# Power_Board.net
KiCad netlist of a schematic drawn in EAGLE
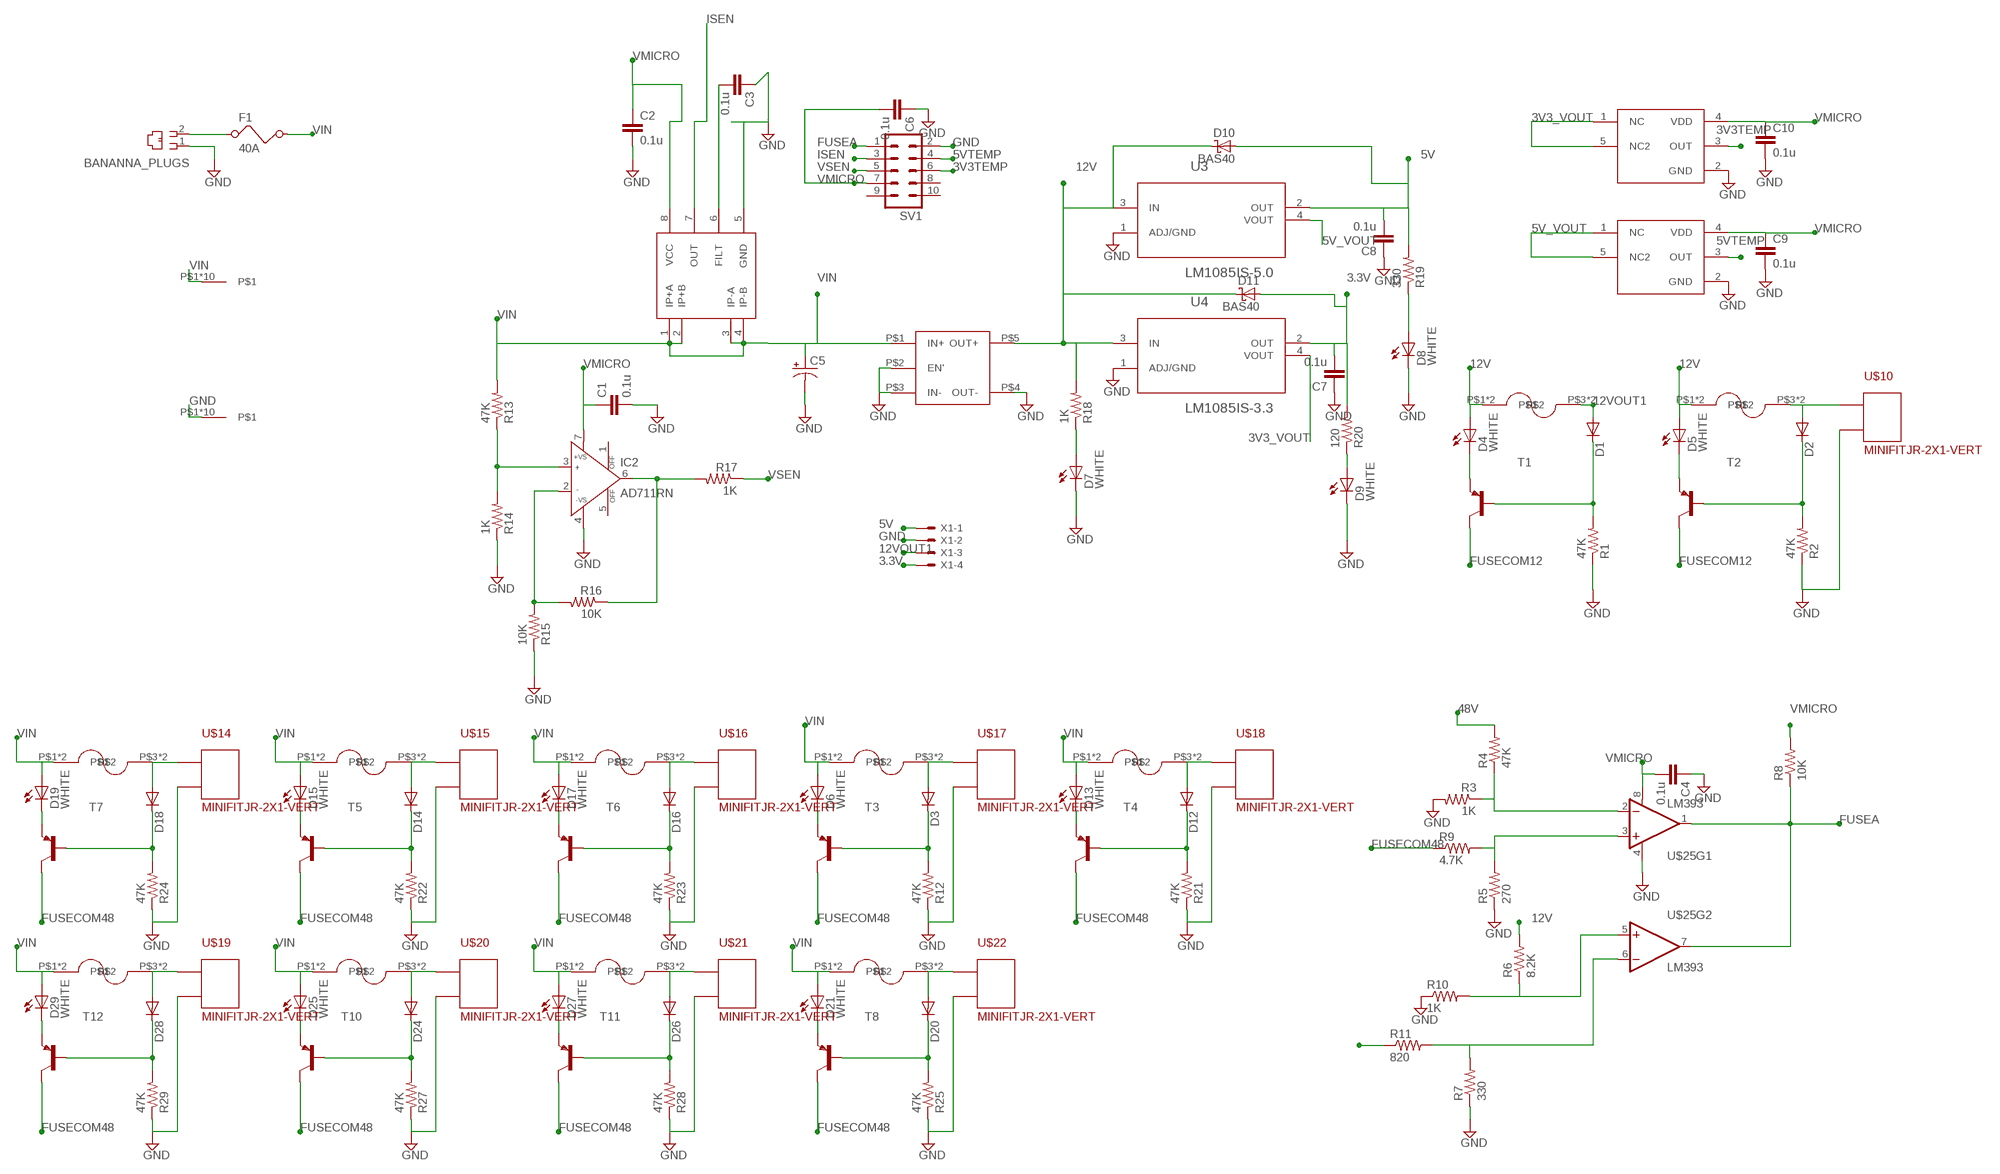
[diagram p0: schematic, sheet 1]

(export (version "E")
  (design (tool "Eeschema 10.0.6"))
  (components
    (comp (ref "BANANNA_PLUGS")
      (value "520470-4")
      (footprint "eagle-import:520470-4")
      (libsource (lib "eagle-import") (part "520470-4"))
    )
    (comp (ref "C1")
      (value "0.1u")
      (footprint "eagle-import:0805")
      (libsource (lib "eagle-import") (part "CAP0805"))
    )
    (comp (ref "C2")
      (value "0.1u")
      (footprint "eagle-import:0805")
      (libsource (lib "eagle-import") (part "CAP0805"))
    )
    (comp (ref "C3")
      (value "0.1u")
      (footprint "eagle-import:0805")
      (libsource (lib "eagle-import") (part "CAP0805"))
    )
    (comp (ref "C4")
      (value "0.1u")
      (footprint "eagle-import:0805")
      (libsource (lib "eagle-import") (part "CAP0805"))
    )
    (comp (ref "C5")
      (value "CPOL-USE10-30")
      (footprint "eagle-import:EB30D")
      (libsource (lib "eagle-import") (part "CPOL-USE10-30"))
    )
    (comp (ref "C6")
      (value "0.1u")
      (footprint "eagle-import:0805")
      (libsource (lib "eagle-import") (part "CAP0805"))
    )
    (comp (ref "C7")
      (value "0.1u")
      (footprint "eagle-import:0805")
      (libsource (lib "eagle-import") (part "CAP0805"))
    )
    (comp (ref "C8")
      (value "0.1u")
      (footprint "eagle-import:0805")
      (libsource (lib "eagle-import") (part "CAP0805"))
    )
    (comp (ref "C9")
      (value "0.1u")
      (footprint "eagle-import:0805")
      (libsource (lib "eagle-import") (part "CAP0805"))
    )
    (comp (ref "C10")
      (value "0.1u")
      (footprint "eagle-import:0805")
      (libsource (lib "eagle-import") (part "CAP0805"))
    )
    (comp (ref "D1")
      (value "DIODEHV")
      (footprint "eagle-import:DIODE-HV")
      (libsource (lib "eagle-import") (part "DIODEHV"))
    )
    (comp (ref "D2")
      (value "DIODEHV")
      (footprint "eagle-import:DIODE-HV")
      (libsource (lib "eagle-import") (part "DIODEHV"))
    )
    (comp (ref "D3")
      (value "DIODEHV")
      (footprint "eagle-import:DIODE-HV")
      (libsource (lib "eagle-import") (part "DIODEHV"))
    )
    (comp (ref "D4")
      (value "WHITE")
      (footprint "eagle-import:LED-1206")
      (libsource (lib "eagle-import") (part "LED-WHITE"))
    )
    (comp (ref "D5")
      (value "WHITE")
      (footprint "eagle-import:LED-1206")
      (libsource (lib "eagle-import") (part "LED-WHITE"))
    )
    (comp (ref "D6")
      (value "WHITE")
      (footprint "eagle-import:LED-1206")
      (libsource (lib "eagle-import") (part "LED-WHITE"))
    )
    (comp (ref "D7")
      (value "WHITE")
      (footprint "eagle-import:LED-1206")
      (libsource (lib "eagle-import") (part "LED-WHITE"))
    )
    (comp (ref "D8")
      (value "WHITE")
      (footprint "eagle-import:LED-1206")
      (libsource (lib "eagle-import") (part "LED-WHITE"))
    )
    (comp (ref "D9")
      (value "WHITE")
      (footprint "eagle-import:LED-1206")
      (libsource (lib "eagle-import") (part "LED-WHITE"))
    )
    (comp (ref "D10")
      (value "BAS40")
      (footprint "eagle-import:SOT23")
      (libsource (lib "eagle-import") (part "BAS40"))
    )
    (comp (ref "D11")
      (value "BAS40")
      (footprint "eagle-import:SOT23")
      (libsource (lib "eagle-import") (part "BAS40"))
    )
    (comp (ref "D12")
      (value "DIODEHV")
      (footprint "eagle-import:DIODE-HV")
      (libsource (lib "eagle-import") (part "DIODEHV"))
    )
    (comp (ref "D13")
      (value "WHITE")
      (footprint "eagle-import:LED-1206")
      (libsource (lib "eagle-import") (part "LED-WHITE"))
    )
    (comp (ref "D14")
      (value "DIODEHV")
      (footprint "eagle-import:DIODE-HV")
      (libsource (lib "eagle-import") (part "DIODEHV"))
    )
    (comp (ref "D15")
      (value "WHITE")
      (footprint "eagle-import:LED-1206")
      (libsource (lib "eagle-import") (part "LED-WHITE"))
    )
    (comp (ref "D16")
      (value "DIODEHV")
      (footprint "eagle-import:DIODE-HV")
      (libsource (lib "eagle-import") (part "DIODEHV"))
    )
    (comp (ref "D17")
      (value "WHITE")
      (footprint "eagle-import:LED-1206")
      (libsource (lib "eagle-import") (part "LED-WHITE"))
    )
    (comp (ref "D18")
      (value "DIODEHV")
      (footprint "eagle-import:DIODE-HV")
      (libsource (lib "eagle-import") (part "DIODEHV"))
    )
    (comp (ref "D19")
      (value "WHITE")
      (footprint "eagle-import:LED-1206")
      (libsource (lib "eagle-import") (part "LED-WHITE"))
    )
    (comp (ref "D20")
      (value "DIODEHV")
      (footprint "eagle-import:DIODE-HV")
      (libsource (lib "eagle-import") (part "DIODEHV"))
    )
    (comp (ref "D21")
      (value "WHITE")
      (footprint "eagle-import:LED-1206")
      (libsource (lib "eagle-import") (part "LED-WHITE"))
    )
    (comp (ref "D24")
      (value "DIODEHV")
      (footprint "eagle-import:DIODE-HV")
      (libsource (lib "eagle-import") (part "DIODEHV"))
    )
    (comp (ref "D25")
      (value "WHITE")
      (footprint "eagle-import:LED-1206")
      (libsource (lib "eagle-import") (part "LED-WHITE"))
    )
    (comp (ref "D26")
      (value "DIODEHV")
      (footprint "eagle-import:DIODE-HV")
      (libsource (lib "eagle-import") (part "DIODEHV"))
    )
    (comp (ref "D27")
      (value "WHITE")
      (footprint "eagle-import:LED-1206")
      (libsource (lib "eagle-import") (part "LED-WHITE"))
    )
    (comp (ref "D28")
      (value "DIODEHV")
      (footprint "eagle-import:DIODE-HV")
      (libsource (lib "eagle-import") (part "DIODEHV"))
    )
    (comp (ref "D29")
      (value "WHITE")
      (footprint "eagle-import:LED-1206")
      (libsource (lib "eagle-import") (part "LED-WHITE"))
    )
    (comp (ref "F1")
      (value "40A")
      (footprint "eagle-import:FUSE")
      (libsource (lib "eagle-import") (part "FUSE"))
    )
    (comp (ref "IC2")
      (value "AD711RN")
      (footprint "eagle-import:SO8")
      (fields (field (name "MF") "ALTERA CORPORATION") (field (name "MPN") "AD711KRZ"))
      (libsource (lib "eagle-import") (part "AD711RN"))
    )
    (comp (ref "R1")
      (value "47K")
      (footprint "eagle-import:0805")
      (libsource (lib "eagle-import") (part "RESISTOR0805-RES"))
    )
    (comp (ref "R2")
      (value "47K")
      (footprint "eagle-import:0805")
      (libsource (lib "eagle-import") (part "RESISTOR0805-RES"))
    )
    (comp (ref "R3")
      (value "1K")
      (footprint "eagle-import:0805")
      (libsource (lib "eagle-import") (part "RESISTOR0805-RES"))
    )
    (comp (ref "R4")
      (value "47K")
      (footprint "eagle-import:0805")
      (libsource (lib "eagle-import") (part "RESISTOR0805-RES"))
    )
    (comp (ref "R5")
      (value "270")
      (footprint "eagle-import:0805")
      (libsource (lib "eagle-import") (part "RESISTOR0805-RES"))
    )
    (comp (ref "R6")
      (value "8.2K")
      (footprint "eagle-import:0805")
      (libsource (lib "eagle-import") (part "RESISTOR0805-RES"))
    )
    (comp (ref "R7")
      (value "330")
      (footprint "eagle-import:0805")
      (libsource (lib "eagle-import") (part "RESISTOR0805-RES"))
    )
    (comp (ref "R8")
      (value "10K")
      (footprint "eagle-import:0805")
      (libsource (lib "eagle-import") (part "RESISTOR0805-RES"))
    )
    (comp (ref "R9")
      (value "4.7K")
      (footprint "eagle-import:0805")
      (libsource (lib "eagle-import") (part "RESISTOR0805-RES"))
    )
    (comp (ref "R10")
      (value "1K")
      (footprint "eagle-import:0805")
      (libsource (lib "eagle-import") (part "RESISTOR0805-RES"))
    )
    (comp (ref "R11")
      (value "820")
      (footprint "eagle-import:0805")
      (libsource (lib "eagle-import") (part "RESISTOR0805-RES"))
    )
    (comp (ref "R12")
      (value "47K")
      (footprint "eagle-import:0805")
      (libsource (lib "eagle-import") (part "RESISTOR0805-RES"))
    )
    (comp (ref "R13")
      (value "47K")
      (footprint "eagle-import:0805")
      (libsource (lib "eagle-import") (part "RESISTOR0805-RES"))
    )
    (comp (ref "R14")
      (value "1K")
      (footprint "eagle-import:0805")
      (libsource (lib "eagle-import") (part "RESISTOR0805-RES"))
    )
    (comp (ref "R15")
      (value "10K")
      (footprint "eagle-import:0805")
      (libsource (lib "eagle-import") (part "RESISTOR0805-RES"))
    )
    (comp (ref "R16")
      (value "10K")
      (footprint "eagle-import:0805")
      (libsource (lib "eagle-import") (part "RESISTOR0805-RES"))
    )
    (comp (ref "R17")
      (value "1K")
      (footprint "eagle-import:0805")
      (libsource (lib "eagle-import") (part "RESISTOR0805-RES"))
    )
    (comp (ref "R18")
      (value "1K")
      (footprint "eagle-import:0805")
      (libsource (lib "eagle-import") (part "RESISTOR0805-RES"))
    )
    (comp (ref "R19")
      (value "330")
      (footprint "eagle-import:0805")
      (libsource (lib "eagle-import") (part "RESISTOR0805-RES"))
    )
    (comp (ref "R20")
      (value "120")
      (footprint "eagle-import:0805")
      (libsource (lib "eagle-import") (part "RESISTOR0805-RES"))
    )
    (comp (ref "R21")
      (value "47K")
      (footprint "eagle-import:0805")
      (libsource (lib "eagle-import") (part "RESISTOR0805-RES"))
    )
    (comp (ref "R22")
      (value "47K")
      (footprint "eagle-import:0805")
      (libsource (lib "eagle-import") (part "RESISTOR0805-RES"))
    )
    (comp (ref "R23")
      (value "47K")
      (footprint "eagle-import:0805")
      (libsource (lib "eagle-import") (part "RESISTOR0805-RES"))
    )
    (comp (ref "R24")
      (value "47K")
      (footprint "eagle-import:0805")
      (libsource (lib "eagle-import") (part "RESISTOR0805-RES"))
    )
    (comp (ref "R25")
      (value "47K")
      (footprint "eagle-import:0805")
      (libsource (lib "eagle-import") (part "RESISTOR0805-RES"))
    )
    (comp (ref "R27")
      (value "47K")
      (footprint "eagle-import:0805")
      (libsource (lib "eagle-import") (part "RESISTOR0805-RES"))
    )
    (comp (ref "R28")
      (value "47K")
      (footprint "eagle-import:0805")
      (libsource (lib "eagle-import") (part "RESISTOR0805-RES"))
    )
    (comp (ref "R29")
      (value "47K")
      (footprint "eagle-import:0805")
      (libsource (lib "eagle-import") (part "RESISTOR0805-RES"))
    )
    (comp (ref "SV1")
      (value "MA05-2")
      (footprint "eagle-import:MA05-2")
      (libsource (lib "eagle-import") (part "MA05-2"))
    )
    (comp (ref "T1")
      (value "BC856BLT1-PNP-SOT23-BEC")
      (footprint "eagle-import:SOT23-BEC")
      (libsource (lib "eagle-import") (part "-PNP-SOT23-BECBC856BLT1"))
    )
    (comp (ref "T2")
      (value "BC856BLT1-PNP-SOT23-BEC")
      (footprint "eagle-import:SOT23-BEC")
      (libsource (lib "eagle-import") (part "-PNP-SOT23-BECBC856BLT1"))
    )
    (comp (ref "T3")
      (value "BC856BLT1-PNP-SOT23-BEC")
      (footprint "eagle-import:SOT23-BEC")
      (libsource (lib "eagle-import") (part "-PNP-SOT23-BECBC856BLT1"))
    )
    (comp (ref "T4")
      (value "BC856BLT1-PNP-SOT23-BEC")
      (footprint "eagle-import:SOT23-BEC")
      (libsource (lib "eagle-import") (part "-PNP-SOT23-BECBC856BLT1"))
    )
    (comp (ref "T5")
      (value "BC856BLT1-PNP-SOT23-BEC")
      (footprint "eagle-import:SOT23-BEC")
      (libsource (lib "eagle-import") (part "-PNP-SOT23-BECBC856BLT1"))
    )
    (comp (ref "T6")
      (value "BC856BLT1-PNP-SOT23-BEC")
      (footprint "eagle-import:SOT23-BEC")
      (libsource (lib "eagle-import") (part "-PNP-SOT23-BECBC856BLT1"))
    )
    (comp (ref "T7")
      (value "BC856BLT1-PNP-SOT23-BEC")
      (footprint "eagle-import:SOT23-BEC")
      (libsource (lib "eagle-import") (part "-PNP-SOT23-BECBC856BLT1"))
    )
    (comp (ref "T8")
      (value "BC856BLT1-PNP-SOT23-BEC")
      (footprint "eagle-import:SOT23-BEC")
      (libsource (lib "eagle-import") (part "-PNP-SOT23-BECBC856BLT1"))
    )
    (comp (ref "T10")
      (value "BC856BLT1-PNP-SOT23-BEC")
      (footprint "eagle-import:SOT23-BEC")
      (libsource (lib "eagle-import") (part "-PNP-SOT23-BECBC856BLT1"))
    )
    (comp (ref "T11")
      (value "BC856BLT1-PNP-SOT23-BEC")
      (footprint "eagle-import:SOT23-BEC")
      (libsource (lib "eagle-import") (part "-PNP-SOT23-BECBC856BLT1"))
    )
    (comp (ref "T12")
      (value "BC856BLT1-PNP-SOT23-BEC")
      (footprint "eagle-import:SOT23-BEC")
      (libsource (lib "eagle-import") (part "-PNP-SOT23-BECBC856BLT1"))
    )
    (comp (ref "U$1")
      (value "SQE48T20120")
      (footprint "eagle-import:BRICK")
      (libsource (lib "eagle-import") (part "SQE48T20120"))
    )
    (comp (ref "U$2")
      (value "FUSEHOLDER3557-2")
      (footprint "eagle-import:FUSEHOLDER3557-2")
      (libsource (lib "eagle-import") (part "FUSEHOLDER3557-2"))
    )
    (comp (ref "U$3")
      (value "FUSEHOLDER3557-2")
      (footprint "eagle-import:FUSEHOLDER3557-2")
      (libsource (lib "eagle-import") (part "FUSEHOLDER3557-2"))
    )
    (comp (ref "U$4")
      (value "FUSEHOLDER3557-2")
      (footprint "eagle-import:FUSEHOLDER3557-2")
      (libsource (lib "eagle-import") (part "FUSEHOLDER3557-2"))
    )
    (comp (ref "U$5")
      (value "FUSEHOLDER3557-2")
      (footprint "eagle-import:FUSEHOLDER3557-2")
      (libsource (lib "eagle-import") (part "FUSEHOLDER3557-2"))
    )
    (comp (ref "U$6")
      (value "FUSEHOLDER3557-2")
      (footprint "eagle-import:FUSEHOLDER3557-2")
      (libsource (lib "eagle-import") (part "FUSEHOLDER3557-2"))
    )
    (comp (ref "U$7")
      (value "FUSEHOLDER3557-2")
      (footprint "eagle-import:FUSEHOLDER3557-2")
      (libsource (lib "eagle-import") (part "FUSEHOLDER3557-2"))
    )
    (comp (ref "U$8")
      (value "FUSEHOLDER3557-2")
      (footprint "eagle-import:FUSEHOLDER3557-2")
      (libsource (lib "eagle-import") (part "FUSEHOLDER3557-2"))
    )
    (comp (ref "U$9")
      (value "FUSEHOLDER3557-2")
      (footprint "eagle-import:FUSEHOLDER3557-2")
      (libsource (lib "eagle-import") (part "FUSEHOLDER3557-2"))
    )
    (comp (ref "U$10")
      (value "MINIFITJR-2X1-VERT")
      (footprint "eagle-import:5566-02B")
      (libsource (lib "eagle-import") (part "MINIFITJR-2X1-VERT"))
    )
    (comp (ref "U$11")
      (value "FUSEHOLDER3557-2")
      (footprint "eagle-import:FUSEHOLDER3557-2")
      (libsource (lib "eagle-import") (part "FUSEHOLDER3557-2"))
    )
    (comp (ref "U$12")
      (value "FUSEHOLDER3557-2")
      (footprint "eagle-import:FUSEHOLDER3557-2")
      (libsource (lib "eagle-import") (part "FUSEHOLDER3557-2"))
    )
    (comp (ref "U$13")
      (value "FUSEHOLDER3557-2")
      (footprint "eagle-import:FUSEHOLDER3557-2")
      (libsource (lib "eagle-import") (part "FUSEHOLDER3557-2"))
    )
    (comp (ref "U$14")
      (value "MINIFITJR-2X1-VERT")
      (footprint "eagle-import:5566-02B")
      (libsource (lib "eagle-import") (part "MINIFITJR-2X1-VERT"))
    )
    (comp (ref "U$15")
      (value "MINIFITJR-2X1-VERT")
      (footprint "eagle-import:5566-02B")
      (libsource (lib "eagle-import") (part "MINIFITJR-2X1-VERT"))
    )
    (comp (ref "U$16")
      (value "MINIFITJR-2X1-VERT")
      (footprint "eagle-import:5566-02B")
      (libsource (lib "eagle-import") (part "MINIFITJR-2X1-VERT"))
    )
    (comp (ref "U$17")
      (value "MINIFITJR-2X1-VERT")
      (footprint "eagle-import:5566-02B")
      (libsource (lib "eagle-import") (part "MINIFITJR-2X1-VERT"))
    )
    (comp (ref "U$18")
      (value "MINIFITJR-2X1-VERT")
      (footprint "eagle-import:5566-02B")
      (libsource (lib "eagle-import") (part "MINIFITJR-2X1-VERT"))
    )
    (comp (ref "U$19")
      (value "MINIFITJR-2X1-VERT")
      (footprint "eagle-import:5566-02B")
      (libsource (lib "eagle-import") (part "MINIFITJR-2X1-VERT"))
    )
    (comp (ref "U$20")
      (value "MINIFITJR-2X1-VERT")
      (footprint "eagle-import:5566-02B")
      (libsource (lib "eagle-import") (part "MINIFITJR-2X1-VERT"))
    )
    (comp (ref "U$21")
      (value "MINIFITJR-2X1-VERT")
      (footprint "eagle-import:5566-02B")
      (libsource (lib "eagle-import") (part "MINIFITJR-2X1-VERT"))
    )
    (comp (ref "U$22")
      (value "MINIFITJR-2X1-VERT")
      (footprint "eagle-import:5566-02B")
      (libsource (lib "eagle-import") (part "MINIFITJR-2X1-VERT"))
    )
    (comp (ref "U$25")
      (value "LM393")
      (footprint "eagle-import:SO08")
      (libsource (lib "eagle-import") (part "LM393"))
    )
    (comp (ref "U$26")
      (value "MCP9700T")
      (footprint "eagle-import:SOT353")
      (libsource (lib "eagle-import") (part "MCP9700T"))
    )
    (comp (ref "U$27")
      (value "MCP9700T")
      (footprint "eagle-import:SOT353")
      (libsource (lib "eagle-import") (part "MCP9700T"))
    )
    (comp (ref "U$30")
      (value "SCREW_TERM")
      (footprint "eagle-import:TERMINAL")
      (libsource (lib "eagle-import") (part "SCREW_TERM"))
    )
    (comp (ref "U$31")
      (value "SCREW_TERM")
      (footprint "eagle-import:TERMINAL")
      (libsource (lib "eagle-import") (part "SCREW_TERM"))
    )
    (comp (ref "U$32")
      (value "ACS713")
      (footprint "eagle-import:SOP08")
      (libsource (lib "eagle-import") (part "ACS713"))
    )
    (comp (ref "U3")
      (value "LM1085IS-5.0")
      (footprint "eagle-import:TO254P1435X457-3N")
      (libsource (lib "eagle-import") (part "LM1085IS-5.0"))
    )
    (comp (ref "U4")
      (value "LM1085IS-3.3")
      (footprint "eagle-import:TO254P1435X457-3N")
      (libsource (lib "eagle-import") (part "LM1085IS-3.3"))
    )
    (comp (ref "X1")
      (value "KK-156-4")
      (footprint "eagle-import:KK-156-4")
      (libsource (lib "eagle-import") (part "KK-156-4"))
    )
  )
  (nets
    (net (code "1") (name "/3.3V") (class "Default")
      (node (ref "C7") (pin "2") (pinfunction "2_2") (pintype "passive"))
      (node (ref "D11") (pin "1") (pinfunction "A_1") (pintype "passive"))
      (node (ref "R20") (pin "2") (pinfunction "2_2") (pintype "passive"))
      (node (ref "U4") (pin "2") (pinfunction "OUT_2") (pintype "output"))
      (node (ref "X1") (pin "4") (pinfunction "S_4") (pintype "passive"))
    )
    (net (code "2") (name "/3V3TEMP") (class "Default")
      (node (ref "SV1") (pin "6") (pinfunction "6_6") (pintype "passive"))
      (node (ref "U$27") (pin "3") (pinfunction "OUT_3") (pintype "bidirectional"))
    )
    (net (code "3") (name "/3V3_VOUT") (class "Default")
      (node (ref "U$27") (pin "1") (pinfunction "NC_1") (pintype "bidirectional"))
      (node (ref "U$27") (pin "5") (pinfunction "NC2_5") (pintype "bidirectional"))
      (node (ref "U4") (pin "4") (pinfunction "VOUT_4") (pintype "output"))
    )
    (net (code "4") (name "/5V") (class "Default")
      (node (ref "C8") (pin "2") (pinfunction "2_2") (pintype "passive"))
      (node (ref "D10") (pin "1") (pinfunction "A_1") (pintype "passive"))
      (node (ref "R19") (pin "2") (pinfunction "2_2") (pintype "passive"))
      (node (ref "U3") (pin "2") (pinfunction "OUT_2") (pintype "output"))
      (node (ref "X1") (pin "1") (pinfunction "S_1") (pintype "passive"))
    )
    (net (code "5") (name "/5VTEMP") (class "Default")
      (node (ref "SV1") (pin "4") (pinfunction "4_4") (pintype "passive"))
      (node (ref "U$26") (pin "3") (pinfunction "OUT_3") (pintype "bidirectional"))
    )
    (net (code "6") (name "/5V_VOUT") (class "Default")
      (node (ref "U$26") (pin "1") (pinfunction "NC_1") (pintype "bidirectional"))
      (node (ref "U$26") (pin "5") (pinfunction "NC2_5") (pintype "bidirectional"))
      (node (ref "U3") (pin "4") (pinfunction "VOUT_4") (pintype "output"))
    )
    (net (code "7") (name "/12V") (class "Default")
      (node (ref "D10") (pin "3") (pinfunction "C_3") (pintype "passive"))
      (node (ref "D11") (pin "3") (pinfunction "C_3") (pintype "passive"))
      (node (ref "D4") (pin "A") (pinfunction "A_A") (pintype "passive"))
      (node (ref "D5") (pin "A") (pinfunction "A_A") (pintype "passive"))
      (node (ref "R18") (pin "2") (pinfunction "2_2") (pintype "passive"))
      (node (ref "R6") (pin "2") (pinfunction "2_2") (pintype "passive"))
      (node (ref "U$1") (pin "P$5") (pinfunction "OUT+_P$5") (pintype "bidirectional"))
      (node (ref "U$3") (pin "P$1") (pinfunction "P$1_P$1") (pintype "bidirectional"))
      (node (ref "U$3") (pin "P$2") (pinfunction "P$1_P$2") (pintype "bidirectional"))
      (node (ref "U$4") (pin "P$1") (pinfunction "P$1_P$1") (pintype "bidirectional"))
      (node (ref "U$4") (pin "P$2") (pinfunction "P$1_P$2") (pintype "bidirectional"))
      (node (ref "U3") (pin "3") (pinfunction "IN_3") (pintype "power_in"))
      (node (ref "U4") (pin "3") (pinfunction "IN_3") (pintype "power_in"))
    )
    (net (code "8") (name "/12VOUT1") (class "Default")
      (node (ref "D1") (pin "A") (pinfunction "A_A") (pintype "passive"))
      (node (ref "U$4") (pin "P$3") (pinfunction "P$2_P$3") (pintype "bidirectional"))
      (node (ref "U$4") (pin "P$4") (pinfunction "P$2_P$4") (pintype "bidirectional"))
      (node (ref "X1") (pin "3") (pinfunction "S_3") (pintype "passive"))
    )
    (net (code "9") (name "/48V") (class "Default")
      (node (ref "R4") (pin "2") (pinfunction "2_2") (pintype "passive"))
    )
    (net (code "10") (name "/FUSEA") (class "Default")
      (node (ref "R8") (pin "1") (pinfunction "1_1") (pintype "passive"))
      (node (ref "SV1") (pin "1") (pinfunction "1_1") (pintype "passive"))
      (node (ref "U$25") (pin "1") (pinfunction "OUT_1") (pintype "output"))
      (node (ref "U$25") (pin "7") (pinfunction "OUT_7") (pintype "output"))
    )
    (net (code "11") (name "/FUSECOM12") (class "Default")
      (node (ref "R11") (pin "1") (pinfunction "1_1") (pintype "passive"))
      (node (ref "T1") (pin "C") (pinfunction "C_C") (pintype "passive"))
      (node (ref "T2") (pin "C") (pinfunction "C_C") (pintype "passive"))
    )
    (net (code "12") (name "/FUSECOM48") (class "Default")
      (node (ref "R9") (pin "1") (pinfunction "1_1") (pintype "passive"))
      (node (ref "T10") (pin "C") (pinfunction "C_C") (pintype "passive"))
      (node (ref "T11") (pin "C") (pinfunction "C_C") (pintype "passive"))
      (node (ref "T12") (pin "C") (pinfunction "C_C") (pintype "passive"))
      (node (ref "T3") (pin "C") (pinfunction "C_C") (pintype "passive"))
      (node (ref "T4") (pin "C") (pinfunction "C_C") (pintype "passive"))
      (node (ref "T5") (pin "C") (pinfunction "C_C") (pintype "passive"))
      (node (ref "T6") (pin "C") (pinfunction "C_C") (pintype "passive"))
      (node (ref "T7") (pin "C") (pinfunction "C_C") (pintype "passive"))
      (node (ref "T8") (pin "C") (pinfunction "C_C") (pintype "passive"))
    )
    (net (code "13") (name "/ISEN") (class "Default")
      (node (ref "SV1") (pin "3") (pinfunction "3_3") (pintype "passive"))
      (node (ref "U$32") (pin "7") (pinfunction "OUT_7") (pintype "bidirectional"))
    )
    (net (code "14") (name "/VIN") (class "Default")
      (node (ref "C5") (pin "+") (pinfunction "+_+") (pintype "passive"))
      (node (ref "D13") (pin "A") (pinfunction "A_A") (pintype "passive"))
      (node (ref "D15") (pin "A") (pinfunction "A_A") (pintype "passive"))
      (node (ref "D17") (pin "A") (pinfunction "A_A") (pintype "passive"))
      (node (ref "D19") (pin "A") (pinfunction "A_A") (pintype "passive"))
      (node (ref "D21") (pin "A") (pinfunction "A_A") (pintype "passive"))
      (node (ref "D25") (pin "A") (pinfunction "A_A") (pintype "passive"))
      (node (ref "D27") (pin "A") (pinfunction "A_A") (pintype "passive"))
      (node (ref "D29") (pin "A") (pinfunction "A_A") (pintype "passive"))
      (node (ref "D6") (pin "A") (pinfunction "A_A") (pintype "passive"))
      (node (ref "F1") (pin "2") (pinfunction "2_2") (pintype "passive"))
      (node (ref "R13") (pin "2") (pinfunction "2_2") (pintype "passive"))
      (node (ref "U$1") (pin "P$1") (pinfunction "IN+_P$1") (pintype "bidirectional"))
      (node (ref "U$11") (pin "P$1") (pinfunction "P$1_P$1") (pintype "bidirectional"))
      (node (ref "U$11") (pin "P$2") (pinfunction "P$1_P$2") (pintype "bidirectional"))
      (node (ref "U$12") (pin "P$1") (pinfunction "P$1_P$1") (pintype "bidirectional"))
      (node (ref "U$12") (pin "P$2") (pinfunction "P$1_P$2") (pintype "bidirectional"))
      (node (ref "U$13") (pin "P$1") (pinfunction "P$1_P$1") (pintype "bidirectional"))
      (node (ref "U$13") (pin "P$2") (pinfunction "P$1_P$2") (pintype "bidirectional"))
      (node (ref "U$2") (pin "P$1") (pinfunction "P$1_P$1") (pintype "bidirectional"))
      (node (ref "U$2") (pin "P$2") (pinfunction "P$1_P$2") (pintype "bidirectional"))
      (node (ref "U$30") (pin "P$1") (pinfunction "P$1_P$1") (pintype "bidirectional"))
      (node (ref "U$30") (pin "P$10") (pinfunction "P$1_P$10") (pintype "bidirectional"))
      (node (ref "U$30") (pin "P$2") (pinfunction "P$1_P$2") (pintype "bidirectional"))
      (node (ref "U$30") (pin "P$3") (pinfunction "P$1_P$3") (pintype "bidirectional"))
      (node (ref "U$30") (pin "P$4") (pinfunction "P$1_P$4") (pintype "bidirectional"))
      (node (ref "U$30") (pin "P$5") (pinfunction "P$1_P$5") (pintype "bidirectional"))
      (node (ref "U$30") (pin "P$6") (pinfunction "P$1_P$6") (pintype "bidirectional"))
      (node (ref "U$30") (pin "P$7") (pinfunction "P$1_P$7") (pintype "bidirectional"))
      (node (ref "U$30") (pin "P$8") (pinfunction "P$1_P$8") (pintype "bidirectional"))
      (node (ref "U$30") (pin "P$9") (pinfunction "P$1_P$9") (pintype "bidirectional"))
      (node (ref "U$32") (pin "1") (pinfunction "IP+A_1") (pintype "bidirectional"))
      (node (ref "U$32") (pin "2") (pinfunction "IP+B_2") (pintype "bidirectional"))
      (node (ref "U$32") (pin "3") (pinfunction "IP-A_3") (pintype "bidirectional"))
      (node (ref "U$32") (pin "4") (pinfunction "IP-B_4") (pintype "bidirectional"))
      (node (ref "U$5") (pin "P$1") (pinfunction "P$1_P$1") (pintype "bidirectional"))
      (node (ref "U$5") (pin "P$2") (pinfunction "P$1_P$2") (pintype "bidirectional"))
      (node (ref "U$6") (pin "P$1") (pinfunction "P$1_P$1") (pintype "bidirectional"))
      (node (ref "U$6") (pin "P$2") (pinfunction "P$1_P$2") (pintype "bidirectional"))
      (node (ref "U$7") (pin "P$1") (pinfunction "P$1_P$1") (pintype "bidirectional"))
      (node (ref "U$7") (pin "P$2") (pinfunction "P$1_P$2") (pintype "bidirectional"))
      (node (ref "U$8") (pin "P$1") (pinfunction "P$1_P$1") (pintype "bidirectional"))
      (node (ref "U$8") (pin "P$2") (pinfunction "P$1_P$2") (pintype "bidirectional"))
      (node (ref "U$9") (pin "P$1") (pinfunction "P$1_P$1") (pintype "bidirectional"))
      (node (ref "U$9") (pin "P$2") (pinfunction "P$1_P$2") (pintype "bidirectional"))
    )
    (net (code "15") (name "/VMICRO") (class "Default")
      (node (ref "C1") (pin "1") (pinfunction "1_1") (pintype "passive"))
      (node (ref "C10") (pin "1") (pinfunction "1_1") (pintype "passive"))
      (node (ref "C2") (pin "1") (pinfunction "1_1") (pintype "passive"))
      (node (ref "C4") (pin "2") (pinfunction "2_2") (pintype "passive"))
      (node (ref "C6") (pin "2") (pinfunction "2_2") (pintype "passive"))
      (node (ref "C9") (pin "1") (pinfunction "1_1") (pintype "passive"))
      (node (ref "IC2") (pin "7") (pinfunction "+VS_7") (pintype "input"))
      (node (ref "R8") (pin "2") (pinfunction "2_2") (pintype "passive"))
      (node (ref "SV1") (pin "7") (pinfunction "7_7") (pintype "passive"))
      (node (ref "U$25") (pin "8") (pinfunction "V+_8") (pintype "power_in"))
      (node (ref "U$26") (pin "4") (pinfunction "VDD_4") (pintype "bidirectional"))
      (node (ref "U$27") (pin "4") (pinfunction "VDD_4") (pintype "bidirectional"))
      (node (ref "U$32") (pin "8") (pinfunction "VCC_8") (pintype "bidirectional"))
    )
    (net (code "16") (name "/VSEN") (class "Default")
      (node (ref "R17") (pin "1") (pinfunction "1_1") (pintype "passive"))
      (node (ref "SV1") (pin "5") (pinfunction "5_5") (pintype "passive"))
    )
    (net (code "17") (name "GND") (class "Default")
      (node (ref "BANANNA_PLUGS") (pin "1") (pinfunction "1_1") (pintype "passive"))
      (node (ref "C1") (pin "2") (pinfunction "2_2") (pintype "passive"))
      (node (ref "C10") (pin "2") (pinfunction "2_2") (pintype "passive"))
      (node (ref "C2") (pin "2") (pinfunction "2_2") (pintype "passive"))
      (node (ref "C3") (pin "1") (pinfunction "1_1") (pintype "passive"))
      (node (ref "C4") (pin "1") (pinfunction "1_1") (pintype "passive"))
      (node (ref "C5") (pin "-") (pinfunction "-_-") (pintype "passive"))
      (node (ref "C6") (pin "1") (pinfunction "1_1") (pintype "passive"))
      (node (ref "C7") (pin "1") (pinfunction "1_1") (pintype "passive"))
      (node (ref "C8") (pin "1") (pinfunction "1_1") (pintype "passive"))
      (node (ref "C9") (pin "2") (pinfunction "2_2") (pintype "passive"))
      (node (ref "D7") (pin "C") (pinfunction "C_C") (pintype "passive"))
      (node (ref "D8") (pin "C") (pinfunction "C_C") (pintype "passive"))
      (node (ref "D9") (pin "C") (pinfunction "C_C") (pintype "passive"))
      (node (ref "IC2") (pin "4") (pinfunction "-VS_4") (pintype "input"))
      (node (ref "R1") (pin "1") (pinfunction "1_1") (pintype "passive"))
      (node (ref "R10") (pin "1") (pinfunction "1_1") (pintype "passive"))
      (node (ref "R12") (pin "1") (pinfunction "1_1") (pintype "passive"))
      (node (ref "R14") (pin "1") (pinfunction "1_1") (pintype "passive"))
      (node (ref "R15") (pin "1") (pinfunction "1_1") (pintype "passive"))
      (node (ref "R2") (pin "1") (pinfunction "1_1") (pintype "passive"))
      (node (ref "R21") (pin "1") (pinfunction "1_1") (pintype "passive"))
      (node (ref "R22") (pin "1") (pinfunction "1_1") (pintype "passive"))
      (node (ref "R23") (pin "1") (pinfunction "1_1") (pintype "passive"))
      (node (ref "R24") (pin "1") (pinfunction "1_1") (pintype "passive"))
      (node (ref "R25") (pin "1") (pinfunction "1_1") (pintype "passive"))
      (node (ref "R27") (pin "1") (pinfunction "1_1") (pintype "passive"))
      (node (ref "R28") (pin "1") (pinfunction "1_1") (pintype "passive"))
      (node (ref "R29") (pin "1") (pinfunction "1_1") (pintype "passive"))
      (node (ref "R3") (pin "2") (pinfunction "2_2") (pintype "passive"))
      (node (ref "R5") (pin "1") (pinfunction "1_1") (pintype "passive"))
      (node (ref "R7") (pin "1") (pinfunction "1_1") (pintype "passive"))
      (node (ref "SV1") (pin "2") (pinfunction "2_2") (pintype "passive"))
      (node (ref "U$1") (pin "P$2") (pinfunction "EN'_P$2") (pintype "bidirectional"))
      (node (ref "U$1") (pin "P$3") (pinfunction "IN-_P$3") (pintype "bidirectional"))
      (node (ref "U$1") (pin "P$4") (pinfunction "OUT-_P$4") (pintype "bidirectional"))
      (node (ref "U$10") (pin "P$2") (pinfunction "P$2_P$2") (pintype "bidirectional"))
      (node (ref "U$14") (pin "P$2") (pinfunction "P$2_P$2") (pintype "bidirectional"))
      (node (ref "U$15") (pin "P$2") (pinfunction "P$2_P$2") (pintype "bidirectional"))
      (node (ref "U$16") (pin "P$2") (pinfunction "P$2_P$2") (pintype "bidirectional"))
      (node (ref "U$17") (pin "P$2") (pinfunction "P$2_P$2") (pintype "bidirectional"))
      (node (ref "U$18") (pin "P$2") (pinfunction "P$2_P$2") (pintype "bidirectional"))
      (node (ref "U$19") (pin "P$2") (pinfunction "P$2_P$2") (pintype "bidirectional"))
      (node (ref "U$20") (pin "P$2") (pinfunction "P$2_P$2") (pintype "bidirectional"))
      (node (ref "U$21") (pin "P$2") (pinfunction "P$2_P$2") (pintype "bidirectional"))
      (node (ref "U$22") (pin "P$2") (pinfunction "P$2_P$2") (pintype "bidirectional"))
      (node (ref "U$25") (pin "4") (pinfunction "V-_4") (pintype "power_in"))
      (node (ref "U$26") (pin "2") (pinfunction "GND_2") (pintype "bidirectional"))
      (node (ref "U$27") (pin "2") (pinfunction "GND_2") (pintype "bidirectional"))
      (node (ref "U$31") (pin "P$1") (pinfunction "P$1_P$1") (pintype "bidirectional"))
      (node (ref "U$31") (pin "P$10") (pinfunction "P$1_P$10") (pintype "bidirectional"))
      (node (ref "U$31") (pin "P$2") (pinfunction "P$1_P$2") (pintype "bidirectional"))
      (node (ref "U$31") (pin "P$3") (pinfunction "P$1_P$3") (pintype "bidirectional"))
      (node (ref "U$31") (pin "P$4") (pinfunction "P$1_P$4") (pintype "bidirectional"))
      (node (ref "U$31") (pin "P$5") (pinfunction "P$1_P$5") (pintype "bidirectional"))
      (node (ref "U$31") (pin "P$6") (pinfunction "P$1_P$6") (pintype "bidirectional"))
      (node (ref "U$31") (pin "P$7") (pinfunction "P$1_P$7") (pintype "bidirectional"))
      (node (ref "U$31") (pin "P$8") (pinfunction "P$1_P$8") (pintype "bidirectional"))
      (node (ref "U$31") (pin "P$9") (pinfunction "P$1_P$9") (pintype "bidirectional"))
      (node (ref "U$32") (pin "5") (pinfunction "GND_5") (pintype "bidirectional"))
      (node (ref "U3") (pin "1") (pinfunction "ADJ/GND_1") (pintype "passive"))
      (node (ref "U4") (pin "1") (pinfunction "ADJ/GND_1") (pintype "passive"))
      (node (ref "X1") (pin "2") (pinfunction "S_2") (pintype "passive"))
    )
    (net (code "18") (name "Net-(BANANNA_PLUGS-Pad2)") (class "Default")
      (node (ref "BANANNA_PLUGS") (pin "2") (pinfunction "2_2") (pintype "passive"))
      (node (ref "F1") (pin "1") (pinfunction "1_1") (pintype "passive"))
    )
    (net (code "19") (name "Net-(D1-PadC)") (class "Default")
      (node (ref "D1") (pin "C") (pinfunction "C_C") (pintype "passive"))
      (node (ref "R1") (pin "2") (pinfunction "2_2") (pintype "passive"))
      (node (ref "T1") (pin "B") (pinfunction "B_B") (pintype "passive"))
    )
    (net (code "20") (name "Net-(D2-PadA)") (class "Default")
      (node (ref "D2") (pin "A") (pinfunction "A_A") (pintype "passive"))
      (node (ref "U$10") (pin "P$1") (pinfunction "P$1_P$1") (pintype "bidirectional"))
      (node (ref "U$3") (pin "P$3") (pinfunction "P$2_P$3") (pintype "bidirectional"))
      (node (ref "U$3") (pin "P$4") (pinfunction "P$2_P$4") (pintype "bidirectional"))
    )
    (net (code "21") (name "Net-(D2-PadC)") (class "Default")
      (node (ref "D2") (pin "C") (pinfunction "C_C") (pintype "passive"))
      (node (ref "R2") (pin "2") (pinfunction "2_2") (pintype "passive"))
      (node (ref "T2") (pin "B") (pinfunction "B_B") (pintype "passive"))
    )
    (net (code "22") (name "Net-(D3-PadA)") (class "Default")
      (node (ref "D3") (pin "A") (pinfunction "A_A") (pintype "passive"))
      (node (ref "U$17") (pin "P$1") (pinfunction "P$1_P$1") (pintype "bidirectional"))
      (node (ref "U$2") (pin "P$3") (pinfunction "P$2_P$3") (pintype "bidirectional"))
      (node (ref "U$2") (pin "P$4") (pinfunction "P$2_P$4") (pintype "bidirectional"))
    )
    (net (code "23") (name "Net-(D3-PadC)") (class "Default")
      (node (ref "D3") (pin "C") (pinfunction "C_C") (pintype "passive"))
      (node (ref "R12") (pin "2") (pinfunction "2_2") (pintype "passive"))
      (node (ref "T3") (pin "B") (pinfunction "B_B") (pintype "passive"))
    )
    (net (code "24") (name "Net-(D4-PadC)") (class "Default")
      (node (ref "D4") (pin "C") (pinfunction "C_C") (pintype "passive"))
      (node (ref "T1") (pin "E") (pinfunction "E_E") (pintype "passive"))
    )
    (net (code "25") (name "Net-(D5-PadC)") (class "Default")
      (node (ref "D5") (pin "C") (pinfunction "C_C") (pintype "passive"))
      (node (ref "T2") (pin "E") (pinfunction "E_E") (pintype "passive"))
    )
    (net (code "26") (name "Net-(D6-PadC)") (class "Default")
      (node (ref "D6") (pin "C") (pinfunction "C_C") (pintype "passive"))
      (node (ref "T3") (pin "E") (pinfunction "E_E") (pintype "passive"))
    )
    (net (code "27") (name "Net-(D7-PadA)") (class "Default")
      (node (ref "D7") (pin "A") (pinfunction "A_A") (pintype "passive"))
      (node (ref "R18") (pin "1") (pinfunction "1_1") (pintype "passive"))
    )
    (net (code "28") (name "Net-(D8-PadA)") (class "Default")
      (node (ref "D8") (pin "A") (pinfunction "A_A") (pintype "passive"))
      (node (ref "R19") (pin "1") (pinfunction "1_1") (pintype "passive"))
    )
    (net (code "29") (name "Net-(D9-PadA)") (class "Default")
      (node (ref "D9") (pin "A") (pinfunction "A_A") (pintype "passive"))
      (node (ref "R20") (pin "1") (pinfunction "1_1") (pintype "passive"))
    )
    (net (code "30") (name "Net-(D12-PadA)") (class "Default")
      (node (ref "D12") (pin "A") (pinfunction "A_A") (pintype "passive"))
      (node (ref "U$18") (pin "P$1") (pinfunction "P$1_P$1") (pintype "bidirectional"))
      (node (ref "U$5") (pin "P$3") (pinfunction "P$2_P$3") (pintype "bidirectional"))
      (node (ref "U$5") (pin "P$4") (pinfunction "P$2_P$4") (pintype "bidirectional"))
    )
    (net (code "31") (name "Net-(D12-PadC)") (class "Default")
      (node (ref "D12") (pin "C") (pinfunction "C_C") (pintype "passive"))
      (node (ref "R21") (pin "2") (pinfunction "2_2") (pintype "passive"))
      (node (ref "T4") (pin "B") (pinfunction "B_B") (pintype "passive"))
    )
    (net (code "32") (name "Net-(D13-PadC)") (class "Default")
      (node (ref "D13") (pin "C") (pinfunction "C_C") (pintype "passive"))
      (node (ref "T4") (pin "E") (pinfunction "E_E") (pintype "passive"))
    )
    (net (code "33") (name "Net-(D14-PadA)") (class "Default")
      (node (ref "D14") (pin "A") (pinfunction "A_A") (pintype "passive"))
      (node (ref "U$15") (pin "P$1") (pinfunction "P$1_P$1") (pintype "bidirectional"))
      (node (ref "U$6") (pin "P$3") (pinfunction "P$2_P$3") (pintype "bidirectional"))
      (node (ref "U$6") (pin "P$4") (pinfunction "P$2_P$4") (pintype "bidirectional"))
    )
    (net (code "34") (name "Net-(D14-PadC)") (class "Default")
      (node (ref "D14") (pin "C") (pinfunction "C_C") (pintype "passive"))
      (node (ref "R22") (pin "2") (pinfunction "2_2") (pintype "passive"))
      (node (ref "T5") (pin "B") (pinfunction "B_B") (pintype "passive"))
    )
    (net (code "35") (name "Net-(D15-PadC)") (class "Default")
      (node (ref "D15") (pin "C") (pinfunction "C_C") (pintype "passive"))
      (node (ref "T5") (pin "E") (pinfunction "E_E") (pintype "passive"))
    )
    (net (code "36") (name "Net-(D16-PadA)") (class "Default")
      (node (ref "D16") (pin "A") (pinfunction "A_A") (pintype "passive"))
      (node (ref "U$16") (pin "P$1") (pinfunction "P$1_P$1") (pintype "bidirectional"))
      (node (ref "U$7") (pin "P$3") (pinfunction "P$2_P$3") (pintype "bidirectional"))
      (node (ref "U$7") (pin "P$4") (pinfunction "P$2_P$4") (pintype "bidirectional"))
    )
    (net (code "37") (name "Net-(D16-PadC)") (class "Default")
      (node (ref "D16") (pin "C") (pinfunction "C_C") (pintype "passive"))
      (node (ref "R23") (pin "2") (pinfunction "2_2") (pintype "passive"))
      (node (ref "T6") (pin "B") (pinfunction "B_B") (pintype "passive"))
    )
    (net (code "38") (name "Net-(D17-PadC)") (class "Default")
      (node (ref "D17") (pin "C") (pinfunction "C_C") (pintype "passive"))
      (node (ref "T6") (pin "E") (pinfunction "E_E") (pintype "passive"))
    )
    (net (code "39") (name "Net-(D18-PadA)") (class "Default")
      (node (ref "D18") (pin "A") (pinfunction "A_A") (pintype "passive"))
      (node (ref "U$14") (pin "P$1") (pinfunction "P$1_P$1") (pintype "bidirectional"))
      (node (ref "U$8") (pin "P$3") (pinfunction "P$2_P$3") (pintype "bidirectional"))
      (node (ref "U$8") (pin "P$4") (pinfunction "P$2_P$4") (pintype "bidirectional"))
    )
    (net (code "40") (name "Net-(D18-PadC)") (class "Default")
      (node (ref "D18") (pin "C") (pinfunction "C_C") (pintype "passive"))
      (node (ref "R24") (pin "2") (pinfunction "2_2") (pintype "passive"))
      (node (ref "T7") (pin "B") (pinfunction "B_B") (pintype "passive"))
    )
    (net (code "41") (name "Net-(D19-PadC)") (class "Default")
      (node (ref "D19") (pin "C") (pinfunction "C_C") (pintype "passive"))
      (node (ref "T7") (pin "E") (pinfunction "E_E") (pintype "passive"))
    )
    (net (code "42") (name "Net-(D20-PadA)") (class "Default")
      (node (ref "D20") (pin "A") (pinfunction "A_A") (pintype "passive"))
      (node (ref "U$22") (pin "P$1") (pinfunction "P$1_P$1") (pintype "bidirectional"))
      (node (ref "U$9") (pin "P$3") (pinfunction "P$2_P$3") (pintype "bidirectional"))
      (node (ref "U$9") (pin "P$4") (pinfunction "P$2_P$4") (pintype "bidirectional"))
    )
    (net (code "43") (name "Net-(D20-PadC)") (class "Default")
      (node (ref "D20") (pin "C") (pinfunction "C_C") (pintype "passive"))
      (node (ref "R25") (pin "2") (pinfunction "2_2") (pintype "passive"))
      (node (ref "T8") (pin "B") (pinfunction "B_B") (pintype "passive"))
    )
    (net (code "44") (name "Net-(D21-PadC)") (class "Default")
      (node (ref "D21") (pin "C") (pinfunction "C_C") (pintype "passive"))
      (node (ref "T8") (pin "E") (pinfunction "E_E") (pintype "passive"))
    )
    (net (code "45") (name "Net-(D24-PadA)") (class "Default")
      (node (ref "D24") (pin "A") (pinfunction "A_A") (pintype "passive"))
      (node (ref "U$11") (pin "P$3") (pinfunction "P$2_P$3") (pintype "bidirectional"))
      (node (ref "U$11") (pin "P$4") (pinfunction "P$2_P$4") (pintype "bidirectional"))
      (node (ref "U$20") (pin "P$1") (pinfunction "P$1_P$1") (pintype "bidirectional"))
    )
    (net (code "46") (name "Net-(D24-PadC)") (class "Default")
      (node (ref "D24") (pin "C") (pinfunction "C_C") (pintype "passive"))
      (node (ref "R27") (pin "2") (pinfunction "2_2") (pintype "passive"))
      (node (ref "T10") (pin "B") (pinfunction "B_B") (pintype "passive"))
    )
    (net (code "47") (name "Net-(D25-PadC)") (class "Default")
      (node (ref "D25") (pin "C") (pinfunction "C_C") (pintype "passive"))
      (node (ref "T10") (pin "E") (pinfunction "E_E") (pintype "passive"))
    )
    (net (code "48") (name "Net-(D26-PadA)") (class "Default")
      (node (ref "D26") (pin "A") (pinfunction "A_A") (pintype "passive"))
      (node (ref "U$12") (pin "P$3") (pinfunction "P$2_P$3") (pintype "bidirectional"))
      (node (ref "U$12") (pin "P$4") (pinfunction "P$2_P$4") (pintype "bidirectional"))
      (node (ref "U$21") (pin "P$1") (pinfunction "P$1_P$1") (pintype "bidirectional"))
    )
    (net (code "49") (name "Net-(D26-PadC)") (class "Default")
      (node (ref "D26") (pin "C") (pinfunction "C_C") (pintype "passive"))
      (node (ref "R28") (pin "2") (pinfunction "2_2") (pintype "passive"))
      (node (ref "T11") (pin "B") (pinfunction "B_B") (pintype "passive"))
    )
    (net (code "50") (name "Net-(D27-PadC)") (class "Default")
      (node (ref "D27") (pin "C") (pinfunction "C_C") (pintype "passive"))
      (node (ref "T11") (pin "E") (pinfunction "E_E") (pintype "passive"))
    )
    (net (code "51") (name "Net-(D28-PadA)") (class "Default")
      (node (ref "D28") (pin "A") (pinfunction "A_A") (pintype "passive"))
      (node (ref "U$13") (pin "P$3") (pinfunction "P$2_P$3") (pintype "bidirectional"))
      (node (ref "U$13") (pin "P$4") (pinfunction "P$2_P$4") (pintype "bidirectional"))
      (node (ref "U$19") (pin "P$1") (pinfunction "P$1_P$1") (pintype "bidirectional"))
    )
    (net (code "52") (name "Net-(D28-PadC)") (class "Default")
      (node (ref "D28") (pin "C") (pinfunction "C_C") (pintype "passive"))
      (node (ref "R29") (pin "2") (pinfunction "2_2") (pintype "passive"))
      (node (ref "T12") (pin "B") (pinfunction "B_B") (pintype "passive"))
    )
    (net (code "53") (name "Net-(D29-PadC)") (class "Default")
      (node (ref "D29") (pin "C") (pinfunction "C_C") (pintype "passive"))
      (node (ref "T12") (pin "E") (pinfunction "E_E") (pintype "passive"))
    )
    (net (code "54") (name "Net-(IC2-IN+)") (class "Default")
      (node (ref "IC2") (pin "3") (pinfunction "IN+_3") (pintype "input"))
      (node (ref "R13") (pin "1") (pinfunction "1_1") (pintype "passive"))
      (node (ref "R14") (pin "2") (pinfunction "2_2") (pintype "passive"))
    )
    (net (code "55") (name "Net-(IC2-IN-)") (class "Default")
      (node (ref "IC2") (pin "2") (pinfunction "IN-_2") (pintype "input"))
      (node (ref "R15") (pin "2") (pinfunction "2_2") (pintype "passive"))
      (node (ref "R16") (pin "2") (pinfunction "2_2") (pintype "passive"))
    )
    (net (code "56") (name "Net-(IC2-OUT)") (class "Default")
      (node (ref "IC2") (pin "6") (pinfunction "OUT_6") (pintype "output"))
      (node (ref "R16") (pin "1") (pinfunction "1_1") (pintype "passive"))
      (node (ref "R17") (pin "2") (pinfunction "2_2") (pintype "passive"))
    )
    (net (code "57") (name "Net-(U$25A-+IN)") (class "Default")
      (node (ref "R5") (pin "2") (pinfunction "2_2") (pintype "passive"))
      (node (ref "R9") (pin "2") (pinfunction "2_2") (pintype "passive"))
      (node (ref "U$25") (pin "3") (pinfunction "+IN_3") (pintype "input"))
    )
    (net (code "58") (name "Net-(U$25A--IN)") (class "Default")
      (node (ref "R3") (pin "1") (pinfunction "1_1") (pintype "passive"))
      (node (ref "R4") (pin "1") (pinfunction "1_1") (pintype "passive"))
      (node (ref "U$25") (pin "2") (pinfunction "-IN_2") (pintype "input"))
    )
    (net (code "59") (name "Net-(U$25B-+IN)") (class "Default")
      (node (ref "R10") (pin "2") (pinfunction "2_2") (pintype "passive"))
      (node (ref "R6") (pin "1") (pinfunction "1_1") (pintype "passive"))
      (node (ref "U$25") (pin "5") (pinfunction "+IN_5") (pintype "input"))
    )
    (net (code "60") (name "Net-(U$25B--IN)") (class "Default")
      (node (ref "R11") (pin "2") (pinfunction "2_2") (pintype "passive"))
      (node (ref "R7") (pin "2") (pinfunction "2_2") (pintype "passive"))
      (node (ref "U$25") (pin "6") (pinfunction "-IN_6") (pintype "input"))
    )
    (net (code "61") (name "Net-(U$32-FILT)") (class "Default")
      (node (ref "C3") (pin "2") (pinfunction "2_2") (pintype "passive"))
      (node (ref "U$32") (pin "6") (pinfunction "FILT_6") (pintype "bidirectional"))
    )
    (net (code "62") (name "unconnected-(IC2-OFF-Pad1)") (class "Default")
      (node (ref "IC2") (pin "1") (pinfunction "OFF_1") (pintype "passive"))
    )
    (net (code "63") (name "unconnected-(IC2-OFF-Pad5)") (class "Default")
      (node (ref "IC2") (pin "5") (pinfunction "OFF_5") (pintype "passive"))
    )
    (net (code "64") (name "unconnected-(SV1-Pad8)") (class "Default")
      (node (ref "SV1") (pin "8") (pinfunction "8_8") (pintype "passive"))
    )
    (net (code "65") (name "unconnected-(SV1-Pad9)") (class "Default")
      (node (ref "SV1") (pin "9") (pinfunction "9_9") (pintype "passive"))
    )
    (net (code "66") (name "unconnected-(SV1-Pad10)") (class "Default")
      (node (ref "SV1") (pin "10") (pinfunction "10_10") (pintype "passive"))
    )
  )
)
